# LEDThermometer.net
KiCad netlist of a schematic drawn in Altium Designer
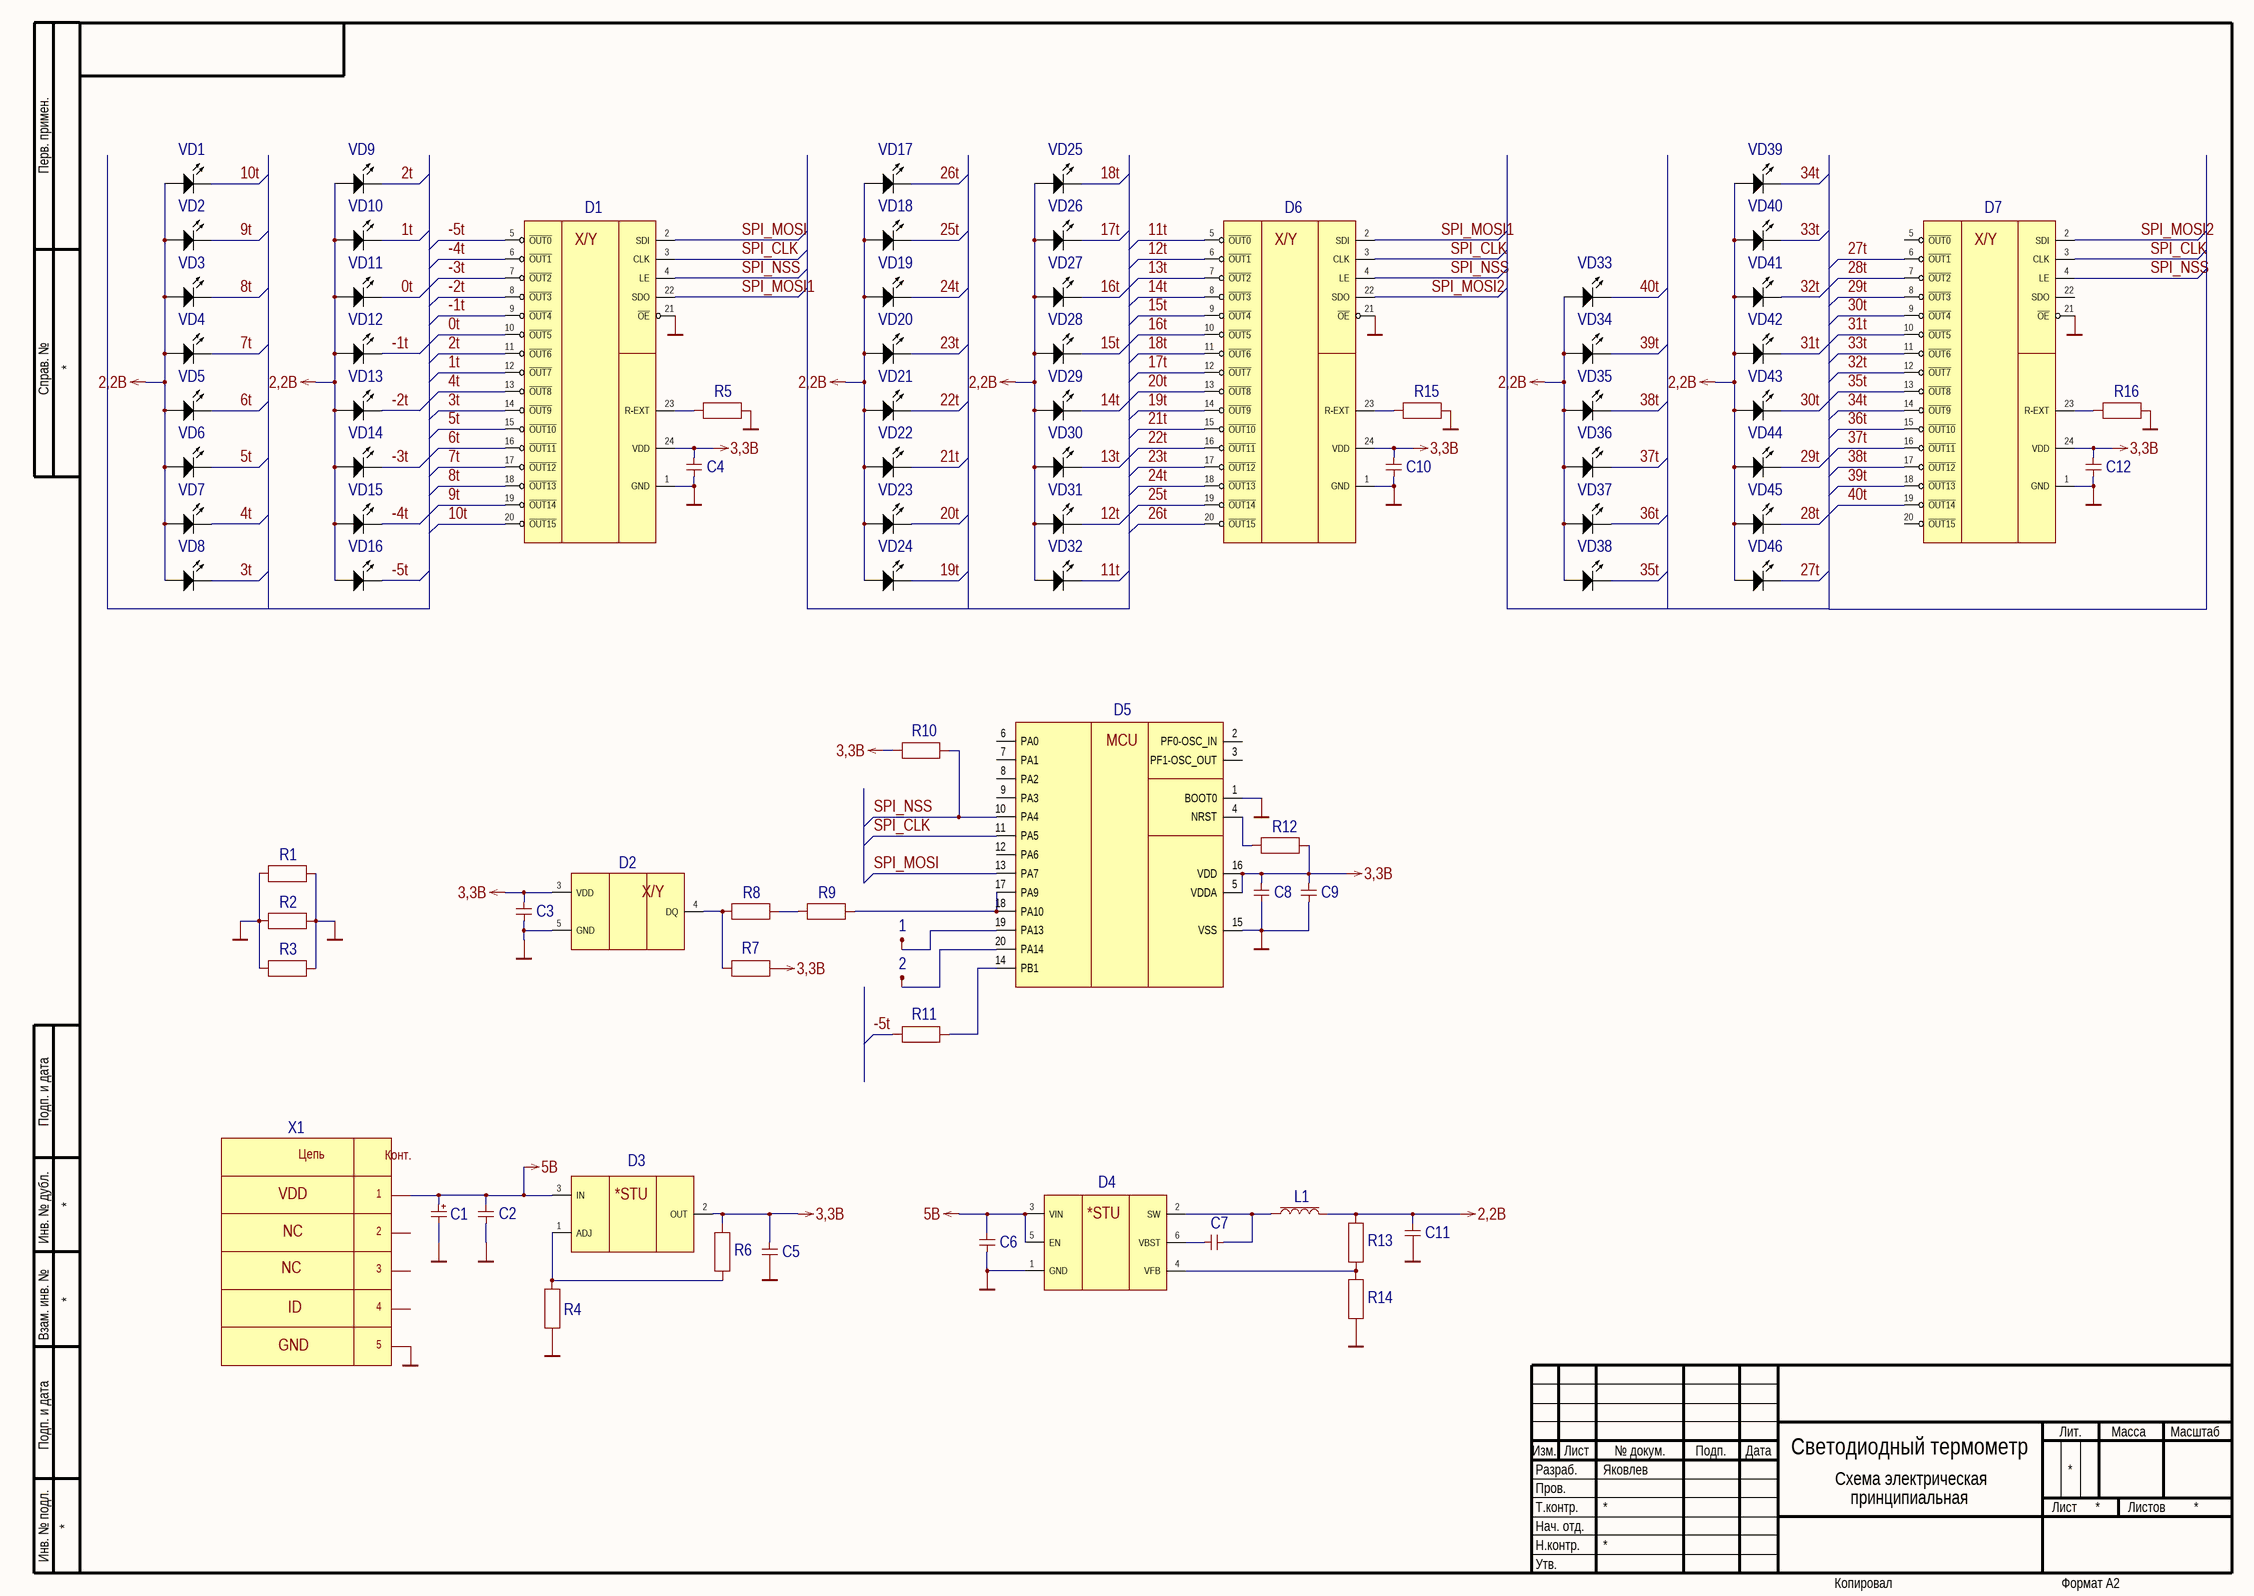
[diagram p0: LEDThermometer.SchDoc]

(export (version "E")
  (design (tool "Eeschema 10.0.6"))
  (components
    (comp (ref "1") (value "*") (footprint "point") (libsource (lib "Passive,Diodes") (part "Point")))
    (comp (ref "2") (value "*") (footprint "point") (libsource (lib "Passive,Diodes") (part "Point")))
    (comp (ref "C1")
      (value "D-20 В-47 мкФ±10 %")
      (footprint "CAP POL 2917/7343")
      (description "Electrolytic capacitor")
      (libsource (lib "Passive,Diodes") (part "Cap_el"))
    )
    (comp (ref "C2")
      (value "0805-16 В-X7R-1мкФ±10 %")
      (footprint "SMD-0805C")
      (description "Capacitor")
      (libsource (lib "Passive,Diodes") (part "Cap"))
    )
    (comp (ref "C3")
      (value "0805-16 В-X7R-0,1мкФ±10 %")
      (footprint "SMD-0805C")
      (description "Capacitor")
      (libsource (lib "Passive,Diodes") (part "Cap"))
    )
    (comp (ref "C4")
      (value "0805-16 В-X7R-0,1мкФ±10 %")
      (footprint "SMD-0805C")
      (description "Capacitor")
      (libsource (lib "Passive,Diodes") (part "Cap"))
    )
    (comp (ref "C5")
      (value "0805-16 В-X7R-1мкФ±10 %")
      (footprint "SMD-0805C")
      (description "Capacitor")
      (libsource (lib "Passive,Diodes") (part "Cap"))
    )
    (comp (ref "C6")
      (value "0805-16 В-X7R-0,1мкФ±10 %")
      (footprint "SMD-0805C")
      (description "Capacitor")
      (libsource (lib "Passive,Diodes") (part "Cap"))
    )
    (comp (ref "C7")
      (value "0805-16 В-X7R-0,1мкФ±10 %")
      (footprint "SMD-0805C")
      (description "Capacitor")
      (libsource (lib "Passive,Diodes") (part "Cap"))
    )
    (comp (ref "C8")
      (value "0805-16 В-X7R-0,1мкФ±10 %")
      (footprint "SMD-0805C")
      (description "Capacitor")
      (libsource (lib "Passive,Diodes") (part "Cap"))
    )
    (comp (ref "C9")
      (value "0805-16 В-X7R-0,1мкФ±10 %")
      (footprint "SMD-0805C")
      (description "Capacitor")
      (libsource (lib "Passive,Diodes") (part "Cap"))
    )
    (comp (ref "C10")
      (value "0805-16 В-X7R-0,1мкФ±10 %")
      (footprint "SMD-0805C")
      (description "Capacitor")
      (libsource (lib "Passive,Diodes") (part "Cap"))
    )
    (comp (ref "C11")
      (value "1206-16 В-X7R-22мкФ±10 %")
      (footprint "SMD-1206C")
      (description "Capacitor")
      (libsource (lib "Passive,Diodes") (part "Cap"))
    )
    (comp (ref "C12")
      (value "0805-16 В-X7R-0,1мкФ±10 %")
      (footprint "SMD-0805C")
      (description "Capacitor")
      (libsource (lib "Passive,Diodes") (part "Cap"))
    )
    (comp (ref "D1")
      (value "MBI5039GF-B")
      (footprint "SOP24L")
      (description "16-Channel Constant Current LED Sink Driver with Silent Error Detection and Current Gain")
      (fields (field (name "MANUFACTURER") "Macroblock"))
      (libsource (lib "Devices") (part "MBI5039"))
    )
    (comp (ref "D2")
      (value "DS18B20Z+")
      (footprint "SO8_M")
      (description "Programmable Resolution 1-Wire Digital Thermometer")
      (fields (field (name "MANUFACTURER") "Maxim Integrated"))
      (libsource (lib "Devices") (part "DS18B20"))
    )
    (comp (ref "D3")
      (value "LM317DCYR")
      (footprint "SOT223_M")
      (description "3-Terminal Adjustable Regulator")
      (fields (field (name "MANUFACTURER") "Texas Instruments"))
      (libsource (lib "Devices") (part "LM317"))
    )
    (comp (ref "D4")
      (value "TPS562200DDCT")
      (footprint "SOT23-6_M")
      (description "4.5-V To 17-V Input, 2-A, 3-A Synchronous Step-Down Voltage Regulator")
      (fields (field (name "MANUFACTURER") "Texas Instruments"))
      (libsource (lib "Devices") (part "TPS562200"))
    )
    (comp (ref "D5")
      (value "STM32F030F4P6")
      (footprint "TSSOP-20")
      (fields (field (name "MANUFACTURER") "STMicroelectronics"))
      (libsource (lib "Devices") (part "STM32F030F"))
    )
    (comp (ref "D6")
      (value "MBI5039GF-B")
      (footprint "SOP24L")
      (description "16-Channel Constant Current LED Sink Driver with Silent Error Detection and Current Gain")
      (fields (field (name "MANUFACTURER") "Macroblock"))
      (libsource (lib "Devices") (part "MBI5039"))
    )
    (comp (ref "D7")
      (value "MBI5039GF-B")
      (footprint "SOP24L")
      (description "16-Channel Constant Current LED Sink Driver with Silent Error Detection and Current Gain")
      (fields (field (name "MANUFACTURER") "Macroblock"))
      (libsource (lib "Devices") (part "MBI5039"))
    )
    (comp (ref "L1")
      (value "NLCV32T-2R2M-EF")
      (footprint "1210_M")
      (description "Inductor")
      (fields (field (name "MANUFACTURER") "TDK"))
      (libsource (lib "Passive,Diodes") (part "Inductor"))
    )
    (comp (ref "R1")
      (value "0805±5 %-0 Ом")
      (footprint "SMD-0805-RES")
      (description "Resistor")
      (libsource (lib "Passive,Diodes") (part "Res"))
    )
    (comp (ref "R2")
      (value "0805±5 %-0 Ом")
      (footprint "SMD-0805-RES")
      (description "Resistor")
      (libsource (lib "Passive,Diodes") (part "Res"))
    )
    (comp (ref "R3")
      (value "0805±5 %-0 Ом")
      (footprint "SMD-0805-RES")
      (description "Resistor")
      (libsource (lib "Passive,Diodes") (part "Res"))
    )
    (comp (ref "R4")
      (value "0805±1 %-2 кОм")
      (footprint "SMD-0805-RES")
      (description "Resistor")
      (libsource (lib "") (part "Res_3"))
    )
    (comp (ref "R5")
      (value "0805±1 %-10 кОм")
      (footprint "SMD-0805-RES")
      (description "Resistor")
      (libsource (lib "Passive,Diodes") (part "Res"))
    )
    (comp (ref "R6")
      (value "0805±1 %-1,3 кОм")
      (footprint "SMD-0805-RES")
      (description "Resistor")
      (libsource (lib "Passive,Diodes") (part "Res"))
    )
    (comp (ref "R7")
      (value "0805±5 %-4,7 кОм")
      (footprint "SMD-0805-RES")
      (description "Resistor")
      (libsource (lib "") (part "Res_2"))
    )
    (comp (ref "R8")
      (value "0805±5 %-0 Ом")
      (footprint "SMD-0805-RES")
      (description "Resistor")
      (libsource (lib "Passive,Diodes") (part "Res"))
    )
    (comp (ref "R9")
      (value "0805±5 %-0 Ом")
      (footprint "SMD-0805-RES")
      (description "Resistor")
      (libsource (lib "Passive,Diodes") (part "Res"))
    )
    (comp (ref "R10")
      (value "0805±5 %-10 кОм")
      (footprint "SMD-0805-RES")
      (description "Resistor")
      (libsource (lib "") (part "Res_1"))
    )
    (comp (ref "R11")
      (value "не устанавливать")
      (footprint "SMD-0805-RES")
      (description "Resistor")
      (libsource (lib "") (part "Res_1"))
    )
    (comp (ref "R12")
      (value "0805±5 %-10 кОм")
      (footprint "SMD-0805-RES")
      (description "Resistor")
      (libsource (lib "Passive,Diodes") (part "Res"))
    )
    (comp (ref "R13")
      (value "0805±1 %-19,6 кОм")
      (footprint "SMD-0805-RES")
      (description "Resistor")
      (libsource (lib "Passive,Diodes") (part "Res"))
    )
    (comp (ref "R14")
      (value "0805±1 %-10,2 кОм")
      (footprint "SMD-0805-RES")
      (description "Resistor")
      (libsource (lib "Passive,Diodes") (part "Res"))
    )
    (comp (ref "R15")
      (value "0805±1 %-10 кОм")
      (footprint "SMD-0805-RES")
      (description "Resistor")
      (libsource (lib "Passive,Diodes") (part "Res"))
    )
    (comp (ref "R16")
      (value "0805±1 %-10 кОм")
      (footprint "SMD-0805-RES")
      (description "Resistor")
      (libsource (lib "Passive,Diodes") (part "Res"))
    )
    (comp (ref "VD1")
      (value "L-144IDT")
      (footprint "LED_1.9x3.9mm")
      (description "Typical INFRARED GaAs LED")
      (fields (field (name "MANUFACTURER") "Kingbright"))
      (libsource (lib "Passive,Diodes") (part "LED"))
    )
    (comp (ref "VD2")
      (value "L-144IDT")
      (footprint "LED_1.9x3.9mm")
      (description "Typical INFRARED GaAs LED")
      (fields (field (name "MANUFACTURER") "Kingbright"))
      (libsource (lib "Passive,Diodes") (part "LED"))
    )
    (comp (ref "VD3")
      (value "L-144IDT")
      (footprint "LED_1.9x3.9mm")
      (description "Typical INFRARED GaAs LED")
      (fields (field (name "MANUFACTURER") "Kingbright"))
      (libsource (lib "Passive,Diodes") (part "LED"))
    )
    (comp (ref "VD4")
      (value "L-144IDT")
      (footprint "LED_1.9x3.9mm")
      (description "Typical INFRARED GaAs LED")
      (fields (field (name "MANUFACTURER") "Kingbright"))
      (libsource (lib "Passive,Diodes") (part "LED"))
    )
    (comp (ref "VD5")
      (value "L-144IDT")
      (footprint "LED_1.9x3.9mm")
      (description "Typical INFRARED GaAs LED")
      (fields (field (name "MANUFACTURER") "Kingbright"))
      (libsource (lib "Passive,Diodes") (part "LED"))
    )
    (comp (ref "VD6")
      (value "L-144IDT")
      (footprint "LED_1.9x3.9mm")
      (description "Typical INFRARED GaAs LED")
      (fields (field (name "MANUFACTURER") "Kingbright"))
      (libsource (lib "Passive,Diodes") (part "LED"))
    )
    (comp (ref "VD7")
      (value "L-144IDT")
      (footprint "LED_1.9x3.9mm")
      (description "Typical INFRARED GaAs LED")
      (fields (field (name "MANUFACTURER") "Kingbright"))
      (libsource (lib "Passive,Diodes") (part "LED"))
    )
    (comp (ref "VD8")
      (value "L-144IDT")
      (footprint "LED_1.9x3.9mm")
      (description "Typical INFRARED GaAs LED")
      (fields (field (name "MANUFACTURER") "Kingbright"))
      (libsource (lib "Passive,Diodes") (part "LED"))
    )
    (comp (ref "VD9")
      (value "L-144IDT")
      (footprint "LED_1.9x3.9mm")
      (description "Typical INFRARED GaAs LED")
      (fields (field (name "MANUFACTURER") "Kingbright"))
      (libsource (lib "Passive,Diodes") (part "LED"))
    )
    (comp (ref "VD10")
      (value "L-144IDT")
      (footprint "LED_1.9x3.9mm")
      (description "Typical INFRARED GaAs LED")
      (fields (field (name "MANUFACTURER") "Kingbright"))
      (libsource (lib "Passive,Diodes") (part "LED"))
    )
    (comp (ref "VD11")
      (value "L-144IDT")
      (footprint "LED_1.9x3.9mm")
      (description "Typical INFRARED GaAs LED")
      (fields (field (name "MANUFACTURER") "Kingbright"))
      (libsource (lib "Passive,Diodes") (part "LED"))
    )
    (comp (ref "VD12")
      (value "L-144IDT")
      (footprint "LED_1.9x3.9mm")
      (description "Typical INFRARED GaAs LED")
      (fields (field (name "MANUFACTURER") "Kingbright"))
      (libsource (lib "Passive,Diodes") (part "LED"))
    )
    (comp (ref "VD13")
      (value "L-144IDT")
      (footprint "LED_1.9x3.9mm")
      (description "Typical INFRARED GaAs LED")
      (fields (field (name "MANUFACTURER") "Kingbright"))
      (libsource (lib "Passive,Diodes") (part "LED"))
    )
    (comp (ref "VD14")
      (value "L-144IDT")
      (footprint "LED_1.9x3.9mm")
      (description "Typical INFRARED GaAs LED")
      (fields (field (name "MANUFACTURER") "Kingbright"))
      (libsource (lib "Passive,Diodes") (part "LED"))
    )
    (comp (ref "VD15")
      (value "L-144IDT")
      (footprint "LED_1.9x3.9mm")
      (description "Typical INFRARED GaAs LED")
      (fields (field (name "MANUFACTURER") "Kingbright"))
      (libsource (lib "Passive,Diodes") (part "LED"))
    )
    (comp (ref "VD16")
      (value "L-793ID")
      (footprint "LED_8mm")
      (description "Typical INFRARED GaAs LED")
      (fields (field (name "MANUFACTURER") "Kingbright"))
      (libsource (lib "Passive,Diodes") (part "LED"))
    )
    (comp (ref "VD17")
      (value "L-144IDT")
      (footprint "LED_1.9x3.9mm")
      (description "Typical INFRARED GaAs LED")
      (fields (field (name "MANUFACTURER") "Kingbright"))
      (libsource (lib "Passive,Diodes") (part "LED"))
    )
    (comp (ref "VD18")
      (value "L-144IDT")
      (footprint "LED_1.9x3.9mm")
      (description "Typical INFRARED GaAs LED")
      (fields (field (name "MANUFACTURER") "Kingbright"))
      (libsource (lib "Passive,Diodes") (part "LED"))
    )
    (comp (ref "VD19")
      (value "L-144IDT")
      (footprint "LED_1.9x3.9mm")
      (description "Typical INFRARED GaAs LED")
      (fields (field (name "MANUFACTURER") "Kingbright"))
      (libsource (lib "Passive,Diodes") (part "LED"))
    )
    (comp (ref "VD20")
      (value "L-144IDT")
      (footprint "LED_1.9x3.9mm")
      (description "Typical INFRARED GaAs LED")
      (fields (field (name "MANUFACTURER") "Kingbright"))
      (libsource (lib "Passive,Diodes") (part "LED"))
    )
    (comp (ref "VD21")
      (value "L-144IDT")
      (footprint "LED_1.9x3.9mm")
      (description "Typical INFRARED GaAs LED")
      (fields (field (name "MANUFACTURER") "Kingbright"))
      (libsource (lib "Passive,Diodes") (part "LED"))
    )
    (comp (ref "VD22")
      (value "L-144IDT")
      (footprint "LED_1.9x3.9mm")
      (description "Typical INFRARED GaAs LED")
      (fields (field (name "MANUFACTURER") "Kingbright"))
      (libsource (lib "Passive,Diodes") (part "LED"))
    )
    (comp (ref "VD23")
      (value "L-144IDT")
      (footprint "LED_1.9x3.9mm")
      (description "Typical INFRARED GaAs LED")
      (fields (field (name "MANUFACTURER") "Kingbright"))
      (libsource (lib "Passive,Diodes") (part "LED"))
    )
    (comp (ref "VD24")
      (value "L-144IDT")
      (footprint "LED_1.9x3.9mm")
      (description "Typical INFRARED GaAs LED")
      (fields (field (name "MANUFACTURER") "Kingbright"))
      (libsource (lib "Passive,Diodes") (part "LED"))
    )
    (comp (ref "VD25")
      (value "L-144IDT")
      (footprint "LED_1.9x3.9mm")
      (description "Typical INFRARED GaAs LED")
      (fields (field (name "MANUFACTURER") "Kingbright"))
      (libsource (lib "Passive,Diodes") (part "LED"))
    )
    (comp (ref "VD26")
      (value "L-144IDT")
      (footprint "LED_1.9x3.9mm")
      (description "Typical INFRARED GaAs LED")
      (fields (field (name "MANUFACTURER") "Kingbright"))
      (libsource (lib "Passive,Diodes") (part "LED"))
    )
    (comp (ref "VD27")
      (value "L-144IDT")
      (footprint "LED_1.9x3.9mm")
      (description "Typical INFRARED GaAs LED")
      (fields (field (name "MANUFACTURER") "Kingbright"))
      (libsource (lib "Passive,Diodes") (part "LED"))
    )
    (comp (ref "VD28")
      (value "L-144IDT")
      (footprint "LED_1.9x3.9mm")
      (description "Typical INFRARED GaAs LED")
      (fields (field (name "MANUFACTURER") "Kingbright"))
      (libsource (lib "Passive,Diodes") (part "LED"))
    )
    (comp (ref "VD29")
      (value "L-144IDT")
      (footprint "LED_1.9x3.9mm")
      (description "Typical INFRARED GaAs LED")
      (fields (field (name "MANUFACTURER") "Kingbright"))
      (libsource (lib "Passive,Diodes") (part "LED"))
    )
    (comp (ref "VD30")
      (value "L-144IDT")
      (footprint "LED_1.9x3.9mm")
      (description "Typical INFRARED GaAs LED")
      (fields (field (name "MANUFACTURER") "Kingbright"))
      (libsource (lib "Passive,Diodes") (part "LED"))
    )
    (comp (ref "VD31")
      (value "L-144IDT")
      (footprint "LED_1.9x3.9mm")
      (description "Typical INFRARED GaAs LED")
      (fields (field (name "MANUFACTURER") "Kingbright"))
      (libsource (lib "Passive,Diodes") (part "LED"))
    )
    (comp (ref "VD32")
      (value "L-144IDT")
      (footprint "LED_1.9x3.9mm")
      (description "Typical INFRARED GaAs LED")
      (fields (field (name "MANUFACTURER") "Kingbright"))
      (libsource (lib "Passive,Diodes") (part "LED"))
    )
    (comp (ref "VD33")
      (value "L-144IDT")
      (footprint "LED_1.9x3.9mm")
      (description "Typical INFRARED GaAs LED")
      (fields (field (name "MANUFACTURER") "Kingbright"))
      (libsource (lib "Passive,Diodes") (part "LED"))
    )
    (comp (ref "VD34")
      (value "L-144IDT")
      (footprint "LED_1.9x3.9mm")
      (description "Typical INFRARED GaAs LED")
      (fields (field (name "MANUFACTURER") "Kingbright"))
      (libsource (lib "Passive,Diodes") (part "LED"))
    )
    (comp (ref "VD35")
      (value "L-144IDT")
      (footprint "LED_1.9x3.9mm")
      (description "Typical INFRARED GaAs LED")
      (fields (field (name "MANUFACTURER") "Kingbright"))
      (libsource (lib "Passive,Diodes") (part "LED"))
    )
    (comp (ref "VD36")
      (value "L-144IDT")
      (footprint "LED_1.9x3.9mm")
      (description "Typical INFRARED GaAs LED")
      (fields (field (name "MANUFACTURER") "Kingbright"))
      (libsource (lib "Passive,Diodes") (part "LED"))
    )
    (comp (ref "VD37")
      (value "L-144IDT")
      (footprint "LED_1.9x3.9mm")
      (description "Typical INFRARED GaAs LED")
      (fields (field (name "MANUFACTURER") "Kingbright"))
      (libsource (lib "Passive,Diodes") (part "LED"))
    )
    (comp (ref "VD38")
      (value "L-144IDT")
      (footprint "LED_1.9x3.9mm")
      (description "Typical INFRARED GaAs LED")
      (fields (field (name "MANUFACTURER") "Kingbright"))
      (libsource (lib "Passive,Diodes") (part "LED"))
    )
    (comp (ref "VD39")
      (value "L-144IDT")
      (footprint "LED_1.9x3.9mm")
      (description "Typical INFRARED GaAs LED")
      (fields (field (name "MANUFACTURER") "Kingbright"))
      (libsource (lib "Passive,Diodes") (part "LED"))
    )
    (comp (ref "VD40")
      (value "L-144IDT")
      (footprint "LED_1.9x3.9mm")
      (description "Typical INFRARED GaAs LED")
      (fields (field (name "MANUFACTURER") "Kingbright"))
      (libsource (lib "Passive,Diodes") (part "LED"))
    )
    (comp (ref "VD41")
      (value "L-144IDT")
      (footprint "LED_1.9x3.9mm")
      (description "Typical INFRARED GaAs LED")
      (fields (field (name "MANUFACTURER") "Kingbright"))
      (libsource (lib "Passive,Diodes") (part "LED"))
    )
    (comp (ref "VD42")
      (value "L-144IDT")
      (footprint "LED_1.9x3.9mm")
      (description "Typical INFRARED GaAs LED")
      (fields (field (name "MANUFACTURER") "Kingbright"))
      (libsource (lib "Passive,Diodes") (part "LED"))
    )
    (comp (ref "VD43")
      (value "L-144IDT")
      (footprint "LED_1.9x3.9mm")
      (description "Typical INFRARED GaAs LED")
      (fields (field (name "MANUFACTURER") "Kingbright"))
      (libsource (lib "Passive,Diodes") (part "LED"))
    )
    (comp (ref "VD44")
      (value "L-144IDT")
      (footprint "LED_1.9x3.9mm")
      (description "Typical INFRARED GaAs LED")
      (fields (field (name "MANUFACTURER") "Kingbright"))
      (libsource (lib "Passive,Diodes") (part "LED"))
    )
    (comp (ref "VD45")
      (value "L-144IDT")
      (footprint "LED_1.9x3.9mm")
      (description "Typical INFRARED GaAs LED")
      (fields (field (name "MANUFACTURER") "Kingbright"))
      (libsource (lib "Passive,Diodes") (part "LED"))
    )
    (comp (ref "VD46")
      (value "L-144IDT")
      (footprint "LED_1.9x3.9mm")
      (description "Typical INFRARED GaAs LED")
      (fields (field (name "MANUFACTURER") "Kingbright"))
      (libsource (lib "Passive,Diodes") (part "LED"))
    )
    (comp (ref "X1")
      (value "DS1104-B60SRS")
      (footprint "Mini-USB-B")
      (description "Mini USB-B connector")
      (fields (field (name "MANUFACTURER") "Connfly Electronics"))
      (libsource (lib "Connectors") (part "MINI-USB-B"))
    )
  )
  (nets
    (net (code "1") (name "/-1t") (class "Default")
      (node (ref "D1") (pin "9") (pinfunction "~{OUT4}_9") (pintype "passive"))
      (node (ref "VD12") (pin "2") (pinfunction "K_2") (pintype "passive"))
    )
    (net (code "2") (name "/-2t") (class "Default")
      (node (ref "D1") (pin "8") (pinfunction "~{OUT3}_8") (pintype "passive"))
      (node (ref "VD13") (pin "2") (pinfunction "K_2") (pintype "passive"))
    )
    (net (code "3") (name "/-3t") (class "Default")
      (node (ref "D1") (pin "7") (pinfunction "~{OUT2}_7") (pintype "passive"))
      (node (ref "VD14") (pin "2") (pinfunction "K_2") (pintype "passive"))
    )
    (net (code "4") (name "/-4t") (class "Default")
      (node (ref "D1") (pin "6") (pinfunction "~{OUT1}_6") (pintype "passive"))
      (node (ref "VD15") (pin "2") (pinfunction "K_2") (pintype "passive"))
    )
    (net (code "5") (name "/-5t") (class "Default")
      (node (ref "D1") (pin "5") (pinfunction "~{OUT0}_5") (pintype "passive"))
      (node (ref "R11") (pin "1") (pinfunction "1_1") (pintype "passive"))
      (node (ref "VD16") (pin "2") (pinfunction "K_2") (pintype "passive"))
    )
    (net (code "6") (name "/0t") (class "Default")
      (node (ref "D1") (pin "10") (pinfunction "~{OUT5}_10") (pintype "passive"))
      (node (ref "VD11") (pin "2") (pinfunction "K_2") (pintype "passive"))
    )
    (net (code "7") (name "/1t") (class "Default")
      (node (ref "D1") (pin "12") (pinfunction "~{OUT7}_12") (pintype "passive"))
      (node (ref "VD10") (pin "2") (pinfunction "K_2") (pintype "passive"))
    )
    (net (code "8") (name "/2t") (class "Default")
      (node (ref "D1") (pin "11") (pinfunction "~{OUT6}_11") (pintype "passive"))
      (node (ref "VD9") (pin "2") (pinfunction "K_2") (pintype "passive"))
    )
    (net (code "9") (name "/3t") (class "Default")
      (node (ref "D1") (pin "14") (pinfunction "~{OUT9}_14") (pintype "passive"))
      (node (ref "VD8") (pin "2") (pinfunction "K_2") (pintype "passive"))
    )
    (net (code "10") (name "/4t") (class "Default")
      (node (ref "D1") (pin "13") (pinfunction "~{OUT8}_13") (pintype "passive"))
      (node (ref "VD7") (pin "2") (pinfunction "K_2") (pintype "passive"))
    )
    (net (code "11") (name "/5t") (class "Default")
      (node (ref "D1") (pin "15") (pinfunction "~{OUT10}_15") (pintype "passive"))
      (node (ref "VD6") (pin "2") (pinfunction "K_2") (pintype "passive"))
    )
    (net (code "12") (name "/6t") (class "Default")
      (node (ref "D1") (pin "16") (pinfunction "~{OUT11}_16") (pintype "passive"))
      (node (ref "VD5") (pin "2") (pinfunction "K_2") (pintype "passive"))
    )
    (net (code "13") (name "/7t") (class "Default")
      (node (ref "D1") (pin "17") (pinfunction "~{OUT12}_17") (pintype "passive"))
      (node (ref "VD4") (pin "2") (pinfunction "K_2") (pintype "passive"))
    )
    (net (code "14") (name "/8t") (class "Default")
      (node (ref "D1") (pin "18") (pinfunction "~{OUT13}_18") (pintype "passive"))
      (node (ref "VD3") (pin "2") (pinfunction "K_2") (pintype "passive"))
    )
    (net (code "15") (name "/9t") (class "Default")
      (node (ref "D1") (pin "19") (pinfunction "~{OUT14}_19") (pintype "passive"))
      (node (ref "VD2") (pin "2") (pinfunction "K_2") (pintype "passive"))
    )
    (net (code "16") (name "/10t") (class "Default")
      (node (ref "D1") (pin "20") (pinfunction "~{OUT15}_20") (pintype "passive"))
      (node (ref "VD1") (pin "2") (pinfunction "K_2") (pintype "passive"))
    )
    (net (code "17") (name "/11t") (class "Default")
      (node (ref "D6") (pin "5") (pinfunction "~{OUT0}_5") (pintype "passive"))
      (node (ref "VD32") (pin "2") (pinfunction "K_2") (pintype "passive"))
    )
    (net (code "18") (name "/12t") (class "Default")
      (node (ref "D6") (pin "6") (pinfunction "~{OUT1}_6") (pintype "passive"))
      (node (ref "VD31") (pin "2") (pinfunction "K_2") (pintype "passive"))
    )
    (net (code "19") (name "/13t") (class "Default")
      (node (ref "D6") (pin "7") (pinfunction "~{OUT2}_7") (pintype "passive"))
      (node (ref "VD30") (pin "2") (pinfunction "K_2") (pintype "passive"))
    )
    (net (code "20") (name "/14t") (class "Default")
      (node (ref "D6") (pin "8") (pinfunction "~{OUT3}_8") (pintype "passive"))
      (node (ref "VD29") (pin "2") (pinfunction "K_2") (pintype "passive"))
    )
    (net (code "21") (name "/15t") (class "Default")
      (node (ref "D6") (pin "9") (pinfunction "~{OUT4}_9") (pintype "passive"))
      (node (ref "VD28") (pin "2") (pinfunction "K_2") (pintype "passive"))
    )
    (net (code "22") (name "/16t") (class "Default")
      (node (ref "D6") (pin "10") (pinfunction "~{OUT5}_10") (pintype "passive"))
      (node (ref "VD27") (pin "2") (pinfunction "K_2") (pintype "passive"))
    )
    (net (code "23") (name "/17t") (class "Default")
      (node (ref "D6") (pin "12") (pinfunction "~{OUT7}_12") (pintype "passive"))
      (node (ref "VD26") (pin "2") (pinfunction "K_2") (pintype "passive"))
    )
    (net (code "24") (name "/18t") (class "Default")
      (node (ref "D6") (pin "11") (pinfunction "~{OUT6}_11") (pintype "passive"))
      (node (ref "VD25") (pin "2") (pinfunction "K_2") (pintype "passive"))
    )
    (net (code "25") (name "/19t") (class "Default")
      (node (ref "D6") (pin "14") (pinfunction "~{OUT9}_14") (pintype "passive"))
      (node (ref "VD24") (pin "2") (pinfunction "K_2") (pintype "passive"))
    )
    (net (code "26") (name "/20t") (class "Default")
      (node (ref "D6") (pin "13") (pinfunction "~{OUT8}_13") (pintype "passive"))
      (node (ref "VD23") (pin "2") (pinfunction "K_2") (pintype "passive"))
    )
    (net (code "27") (name "/21t") (class "Default")
      (node (ref "D6") (pin "15") (pinfunction "~{OUT10}_15") (pintype "passive"))
      (node (ref "VD22") (pin "2") (pinfunction "K_2") (pintype "passive"))
    )
    (net (code "28") (name "/22t") (class "Default")
      (node (ref "D6") (pin "16") (pinfunction "~{OUT11}_16") (pintype "passive"))
      (node (ref "VD21") (pin "2") (pinfunction "K_2") (pintype "passive"))
    )
    (net (code "29") (name "/23t") (class "Default")
      (node (ref "D6") (pin "17") (pinfunction "~{OUT12}_17") (pintype "passive"))
      (node (ref "VD20") (pin "2") (pinfunction "K_2") (pintype "passive"))
    )
    (net (code "30") (name "/24t") (class "Default")
      (node (ref "D6") (pin "18") (pinfunction "~{OUT13}_18") (pintype "passive"))
      (node (ref "VD19") (pin "2") (pinfunction "K_2") (pintype "passive"))
    )
    (net (code "31") (name "/25t") (class "Default")
      (node (ref "D6") (pin "19") (pinfunction "~{OUT14}_19") (pintype "passive"))
      (node (ref "VD18") (pin "2") (pinfunction "K_2") (pintype "passive"))
    )
    (net (code "32") (name "/26t") (class "Default")
      (node (ref "D6") (pin "20") (pinfunction "~{OUT15}_20") (pintype "passive"))
      (node (ref "VD17") (pin "2") (pinfunction "K_2") (pintype "passive"))
    )
    (net (code "33") (name "/27t") (class "Default")
      (node (ref "D7") (pin "6") (pinfunction "~{OUT1}_6") (pintype "passive"))
      (node (ref "VD46") (pin "2") (pinfunction "K_2") (pintype "passive"))
    )
    (net (code "34") (name "/28t") (class "Default")
      (node (ref "D7") (pin "7") (pinfunction "~{OUT2}_7") (pintype "passive"))
      (node (ref "VD45") (pin "2") (pinfunction "K_2") (pintype "passive"))
    )
    (net (code "35") (name "/29t") (class "Default")
      (node (ref "D7") (pin "8") (pinfunction "~{OUT3}_8") (pintype "passive"))
      (node (ref "VD44") (pin "2") (pinfunction "K_2") (pintype "passive"))
    )
    (net (code "36") (name "/30t") (class "Default")
      (node (ref "D7") (pin "9") (pinfunction "~{OUT4}_9") (pintype "passive"))
      (node (ref "VD43") (pin "2") (pinfunction "K_2") (pintype "passive"))
    )
    (net (code "37") (name "/31t") (class "Default")
      (node (ref "D7") (pin "10") (pinfunction "~{OUT5}_10") (pintype "passive"))
      (node (ref "VD42") (pin "2") (pinfunction "K_2") (pintype "passive"))
    )
    (net (code "38") (name "/32t") (class "Default")
      (node (ref "D7") (pin "12") (pinfunction "~{OUT7}_12") (pintype "passive"))
      (node (ref "VD41") (pin "2") (pinfunction "K_2") (pintype "passive"))
    )
    (net (code "39") (name "/33t") (class "Default")
      (node (ref "D7") (pin "11") (pinfunction "~{OUT6}_11") (pintype "passive"))
      (node (ref "VD40") (pin "2") (pinfunction "K_2") (pintype "passive"))
    )
    (net (code "40") (name "/34t") (class "Default")
      (node (ref "D7") (pin "14") (pinfunction "~{OUT9}_14") (pintype "passive"))
      (node (ref "VD39") (pin "2") (pinfunction "K_2") (pintype "passive"))
    )
    (net (code "41") (name "/35t") (class "Default")
      (node (ref "D7") (pin "13") (pinfunction "~{OUT8}_13") (pintype "passive"))
      (node (ref "VD38") (pin "2") (pinfunction "K_2") (pintype "passive"))
    )
    (net (code "42") (name "/36t") (class "Default")
      (node (ref "D7") (pin "15") (pinfunction "~{OUT10}_15") (pintype "passive"))
      (node (ref "VD37") (pin "2") (pinfunction "K_2") (pintype "passive"))
    )
    (net (code "43") (name "/37t") (class "Default")
      (node (ref "D7") (pin "16") (pinfunction "~{OUT11}_16") (pintype "passive"))
      (node (ref "VD36") (pin "2") (pinfunction "K_2") (pintype "passive"))
    )
    (net (code "44") (name "/38t") (class "Default")
      (node (ref "D7") (pin "17") (pinfunction "~{OUT12}_17") (pintype "passive"))
      (node (ref "VD35") (pin "2") (pinfunction "K_2") (pintype "passive"))
    )
    (net (code "45") (name "/39t") (class "Default")
      (node (ref "D7") (pin "18") (pinfunction "~{OUT13}_18") (pintype "passive"))
      (node (ref "VD34") (pin "2") (pinfunction "K_2") (pintype "passive"))
    )
    (net (code "46") (name "/40t") (class "Default")
      (node (ref "D7") (pin "19") (pinfunction "~{OUT14}_19") (pintype "passive"))
      (node (ref "VD33") (pin "2") (pinfunction "K_2") (pintype "passive"))
    )
    (net (code "47") (name "/SPI_CLK") (class "Default")
      (node (ref "D1") (pin "3") (pinfunction "CLK_3") (pintype "passive"))
      (node (ref "D5") (pin "11") (pinfunction "PA5_11") (pintype "passive"))
      (node (ref "D6") (pin "3") (pinfunction "CLK_3") (pintype "passive"))
      (node (ref "D7") (pin "3") (pinfunction "CLK_3") (pintype "passive"))
    )
    (net (code "48") (name "/SPI_MOSI") (class "Default")
      (node (ref "D1") (pin "2") (pinfunction "SDI_2") (pintype "passive"))
      (node (ref "D5") (pin "13") (pinfunction "PA7_13") (pintype "passive"))
    )
    (net (code "49") (name "/SPI_MOSI1") (class "Default")
      (node (ref "D1") (pin "22") (pinfunction "SDO_22") (pintype "passive"))
      (node (ref "D6") (pin "2") (pinfunction "SDI_2") (pintype "passive"))
    )
    (net (code "50") (name "/SPI_MOSI2") (class "Default")
      (node (ref "D6") (pin "22") (pinfunction "SDO_22") (pintype "passive"))
      (node (ref "D7") (pin "2") (pinfunction "SDI_2") (pintype "passive"))
    )
    (net (code "51") (name "/SPI_NSS") (class "Default")
      (node (ref "D1") (pin "4") (pinfunction "LE_4") (pintype "passive"))
      (node (ref "D5") (pin "10") (pinfunction "PA4_10") (pintype "passive"))
      (node (ref "D6") (pin "4") (pinfunction "LE_4") (pintype "passive"))
      (node (ref "D7") (pin "4") (pinfunction "LE_4") (pintype "passive"))
      (node (ref "R10") (pin "2") (pinfunction "2_2") (pintype "passive"))
    )
    (net (code "52") (name "2,2В") (class "Default")
      (node (ref "C11") (pin "2") (pinfunction "2_2") (pintype "passive"))
      (node (ref "L1") (pin "2") (pinfunction "2_2") (pintype "passive"))
      (node (ref "R13") (pin "2") (pinfunction "2_2") (pintype "passive"))
      (node (ref "VD1") (pin "1") (pinfunction "A_1") (pintype "passive"))
      (node (ref "VD10") (pin "1") (pinfunction "A_1") (pintype "passive"))
      (node (ref "VD11") (pin "1") (pinfunction "A_1") (pintype "passive"))
      (node (ref "VD12") (pin "1") (pinfunction "A_1") (pintype "passive"))
      (node (ref "VD13") (pin "1") (pinfunction "A_1") (pintype "passive"))
      (node (ref "VD14") (pin "1") (pinfunction "A_1") (pintype "passive"))
      (node (ref "VD15") (pin "1") (pinfunction "A_1") (pintype "passive"))
      (node (ref "VD16") (pin "1") (pinfunction "A_1") (pintype "passive"))
      (node (ref "VD17") (pin "1") (pinfunction "A_1") (pintype "passive"))
      (node (ref "VD18") (pin "1") (pinfunction "A_1") (pintype "passive"))
      (node (ref "VD19") (pin "1") (pinfunction "A_1") (pintype "passive"))
      (node (ref "VD2") (pin "1") (pinfunction "A_1") (pintype "passive"))
      (node (ref "VD20") (pin "1") (pinfunction "A_1") (pintype "passive"))
      (node (ref "VD21") (pin "1") (pinfunction "A_1") (pintype "passive"))
      (node (ref "VD22") (pin "1") (pinfunction "A_1") (pintype "passive"))
      (node (ref "VD23") (pin "1") (pinfunction "A_1") (pintype "passive"))
      (node (ref "VD24") (pin "1") (pinfunction "A_1") (pintype "passive"))
      (node (ref "VD25") (pin "1") (pinfunction "A_1") (pintype "passive"))
      (node (ref "VD26") (pin "1") (pinfunction "A_1") (pintype "passive"))
      (node (ref "VD27") (pin "1") (pinfunction "A_1") (pintype "passive"))
      (node (ref "VD28") (pin "1") (pinfunction "A_1") (pintype "passive"))
      (node (ref "VD29") (pin "1") (pinfunction "A_1") (pintype "passive"))
      (node (ref "VD3") (pin "1") (pinfunction "A_1") (pintype "passive"))
      (node (ref "VD30") (pin "1") (pinfunction "A_1") (pintype "passive"))
      (node (ref "VD31") (pin "1") (pinfunction "A_1") (pintype "passive"))
      (node (ref "VD32") (pin "1") (pinfunction "A_1") (pintype "passive"))
      (node (ref "VD33") (pin "1") (pinfunction "A_1") (pintype "passive"))
      (node (ref "VD34") (pin "1") (pinfunction "A_1") (pintype "passive"))
      (node (ref "VD35") (pin "1") (pinfunction "A_1") (pintype "passive"))
      (node (ref "VD36") (pin "1") (pinfunction "A_1") (pintype "passive"))
      (node (ref "VD37") (pin "1") (pinfunction "A_1") (pintype "passive"))
      (node (ref "VD38") (pin "1") (pinfunction "A_1") (pintype "passive"))
      (node (ref "VD39") (pin "1") (pinfunction "A_1") (pintype "passive"))
      (node (ref "VD4") (pin "1") (pinfunction "A_1") (pintype "passive"))
      (node (ref "VD40") (pin "1") (pinfunction "A_1") (pintype "passive"))
      (node (ref "VD41") (pin "1") (pinfunction "A_1") (pintype "passive"))
      (node (ref "VD42") (pin "1") (pinfunction "A_1") (pintype "passive"))
      (node (ref "VD43") (pin "1") (pinfunction "A_1") (pintype "passive"))
      (node (ref "VD44") (pin "1") (pinfunction "A_1") (pintype "passive"))
      (node (ref "VD45") (pin "1") (pinfunction "A_1") (pintype "passive"))
      (node (ref "VD46") (pin "1") (pinfunction "A_1") (pintype "passive"))
      (node (ref "VD5") (pin "1") (pinfunction "A_1") (pintype "passive"))
      (node (ref "VD6") (pin "1") (pinfunction "A_1") (pintype "passive"))
      (node (ref "VD7") (pin "1") (pinfunction "A_1") (pintype "passive"))
      (node (ref "VD8") (pin "1") (pinfunction "A_1") (pintype "passive"))
      (node (ref "VD9") (pin "1") (pinfunction "A_1") (pintype "passive"))
    )
    (net (code "53") (name "3,3В") (class "Default")
      (node (ref "C10") (pin "2") (pinfunction "2_2") (pintype "passive"))
      (node (ref "C12") (pin "2") (pinfunction "2_2") (pintype "passive"))
      (node (ref "C3") (pin "2") (pinfunction "2_2") (pintype "passive"))
      (node (ref "C4") (pin "2") (pinfunction "2_2") (pintype "passive"))
      (node (ref "C5") (pin "2") (pinfunction "2_2") (pintype "passive"))
      (node (ref "C8") (pin "2") (pinfunction "2_2") (pintype "passive"))
      (node (ref "C9") (pin "2") (pinfunction "2_2") (pintype "passive"))
      (node (ref "D1") (pin "24") (pinfunction "VDD_24") (pintype "power_in"))
      (node (ref "D2") (pin "3") (pinfunction "VDD_3") (pintype "passive"))
      (node (ref "D3") (pin "2") (pinfunction "OUT_2") (pintype "power_in"))
      (node (ref "D5") (pin "16") (pinfunction "VDD_16") (pintype "power_in"))
      (node (ref "D5") (pin "5") (pinfunction "VDDA_5") (pintype "power_in"))
      (node (ref "D6") (pin "24") (pinfunction "VDD_24") (pintype "power_in"))
      (node (ref "D7") (pin "24") (pinfunction "VDD_24") (pintype "power_in"))
      (node (ref "R10") (pin "1") (pinfunction "1_1") (pintype "passive"))
      (node (ref "R12") (pin "2") (pinfunction "2_2") (pintype "passive"))
      (node (ref "R6") (pin "2") (pinfunction "2_2") (pintype "passive"))
      (node (ref "R7") (pin "1") (pinfunction "1_1") (pintype "passive"))
    )
    (net (code "54") (name "5В") (class "Default")
      (node (ref "C1") (pin "1") (pinfunction "1_1") (pintype "passive"))
      (node (ref "C2") (pin "2") (pinfunction "2_2") (pintype "passive"))
      (node (ref "C6") (pin "2") (pinfunction "2_2") (pintype "passive"))
      (node (ref "D3") (pin "3") (pinfunction "IN_3") (pintype "power_in"))
      (node (ref "D4") (pin "3") (pinfunction "VIN_3") (pintype "power_in"))
      (node (ref "D4") (pin "5") (pinfunction "EN_5") (pintype "passive"))
      (node (ref "X1") (pin "1") (pinfunction "1_1") (pintype "passive"))
    )
    (net (code "55") (name "GND") (class "Default")
      (node (ref "C1") (pin "2") (pinfunction "2_2") (pintype "passive"))
      (node (ref "C10") (pin "1") (pinfunction "1_1") (pintype "passive"))
      (node (ref "C11") (pin "1") (pinfunction "1_1") (pintype "passive"))
      (node (ref "C12") (pin "1") (pinfunction "1_1") (pintype "passive"))
      (node (ref "C2") (pin "1") (pinfunction "1_1") (pintype "passive"))
      (node (ref "C3") (pin "1") (pinfunction "1_1") (pintype "passive"))
      (node (ref "C4") (pin "1") (pinfunction "1_1") (pintype "passive"))
      (node (ref "C5") (pin "1") (pinfunction "1_1") (pintype "passive"))
      (node (ref "C6") (pin "1") (pinfunction "1_1") (pintype "passive"))
      (node (ref "C8") (pin "1") (pinfunction "1_1") (pintype "passive"))
      (node (ref "C9") (pin "1") (pinfunction "1_1") (pintype "passive"))
      (node (ref "D1") (pin "1") (pinfunction "GND_1") (pintype "power_in"))
      (node (ref "D1") (pin "21") (pinfunction "~{OE}_21") (pintype "passive"))
      (node (ref "D2") (pin "5") (pinfunction "GND_5") (pintype "power_in"))
      (node (ref "D4") (pin "1") (pinfunction "GND_1") (pintype "power_in"))
      (node (ref "D5") (pin "1") (pinfunction "BOOT0_1") (pintype "passive"))
      (node (ref "D5") (pin "15") (pinfunction "VSS_15") (pintype "power_in"))
      (node (ref "D6") (pin "1") (pinfunction "GND_1") (pintype "power_in"))
      (node (ref "D6") (pin "21") (pinfunction "~{OE}_21") (pintype "passive"))
      (node (ref "D7") (pin "1") (pinfunction "GND_1") (pintype "power_in"))
      (node (ref "D7") (pin "21") (pinfunction "~{OE}_21") (pintype "passive"))
      (node (ref "R1") (pin "1") (pinfunction "1_1") (pintype "passive"))
      (node (ref "R1") (pin "2") (pinfunction "2_2") (pintype "passive"))
      (node (ref "R14") (pin "1") (pinfunction "1_1") (pintype "passive"))
      (node (ref "R15") (pin "2") (pinfunction "2_2") (pintype "passive"))
      (node (ref "R16") (pin "2") (pinfunction "2_2") (pintype "passive"))
      (node (ref "R2") (pin "1") (pinfunction "1_1") (pintype "passive"))
      (node (ref "R2") (pin "2") (pinfunction "2_2") (pintype "passive"))
      (node (ref "R3") (pin "1") (pinfunction "1_1") (pintype "passive"))
      (node (ref "R3") (pin "2") (pinfunction "2_2") (pintype "passive"))
      (node (ref "R4") (pin "2") (pinfunction "2_2") (pintype "passive"))
      (node (ref "R5") (pin "2") (pinfunction "2_2") (pintype "passive"))
      (node (ref "X1") (pin "5") (pinfunction "5_5") (pintype "passive"))
    )
    (net (code "56") (name "Net-(D1-R-EXT)") (class "Default")
      (node (ref "D1") (pin "23") (pinfunction "R-EXT_23") (pintype "passive"))
      (node (ref "R5") (pin "1") (pinfunction "1_1") (pintype "passive"))
    )
    (net (code "57") (name "Net-(D2-DQ)") (class "Default")
      (node (ref "D2") (pin "4") (pinfunction "DQ_4") (pintype "passive"))
      (node (ref "R7") (pin "2") (pinfunction "2_2") (pintype "passive"))
      (node (ref "R8") (pin "1") (pinfunction "1_1") (pintype "passive"))
    )
    (net (code "58") (name "Net-(D3-ADJ)") (class "Default")
      (node (ref "D3") (pin "1") (pinfunction "ADJ_1") (pintype "passive"))
      (node (ref "R4") (pin "1") (pinfunction "1_1") (pintype "passive"))
      (node (ref "R6") (pin "1") (pinfunction "1_1") (pintype "passive"))
    )
    (net (code "59") (name "Net-(D4-SW)") (class "Default")
      (node (ref "C7") (pin "1") (pinfunction "1_1") (pintype "passive"))
      (node (ref "D4") (pin "2") (pinfunction "SW_2") (pintype "passive"))
      (node (ref "L1") (pin "1") (pinfunction "1_1") (pintype "passive"))
    )
    (net (code "60") (name "Net-(D4-VBST)") (class "Default")
      (node (ref "C7") (pin "2") (pinfunction "2_2") (pintype "passive"))
      (node (ref "D4") (pin "6") (pinfunction "VBST_6") (pintype "passive"))
    )
    (net (code "61") (name "Net-(D4-VFB)") (class "Default")
      (node (ref "D4") (pin "4") (pinfunction "VFB_4") (pintype "passive"))
      (node (ref "R13") (pin "1") (pinfunction "1_1") (pintype "passive"))
      (node (ref "R14") (pin "2") (pinfunction "2_2") (pintype "passive"))
    )
    (net (code "62") (name "Net-(D5-NRST)") (class "Default")
      (node (ref "D5") (pin "4") (pinfunction "NRST_4") (pintype "passive"))
      (node (ref "R12") (pin "1") (pinfunction "1_1") (pintype "passive"))
    )
    (net (code "63") (name "Net-(D5-PA10)") (class "Default")
      (node (ref "D5") (pin "17") (pinfunction "PA9_17") (pintype "passive"))
      (node (ref "D5") (pin "18") (pinfunction "PA10_18") (pintype "passive"))
      (node (ref "R9") (pin "2") (pinfunction "2_2") (pintype "passive"))
    )
    (net (code "64") (name "Net-(D5-PA13)") (class "Default")
      (node (ref "1") (pin "1") (pintype "passive"))
      (node (ref "D5") (pin "19") (pinfunction "PA13_19") (pintype "passive"))
    )
    (net (code "65") (name "Net-(D5-PA14)") (class "Default")
      (node (ref "2") (pin "1") (pintype "passive"))
      (node (ref "D5") (pin "20") (pinfunction "PA14_20") (pintype "passive"))
    )
    (net (code "66") (name "Net-(D5-PB1)") (class "Default")
      (node (ref "D5") (pin "14") (pinfunction "PB1_14") (pintype "passive"))
      (node (ref "R11") (pin "2") (pinfunction "2_2") (pintype "passive"))
    )
    (net (code "67") (name "Net-(D6-R-EXT)") (class "Default")
      (node (ref "D6") (pin "23") (pinfunction "R-EXT_23") (pintype "passive"))
      (node (ref "R15") (pin "1") (pinfunction "1_1") (pintype "passive"))
    )
    (net (code "68") (name "Net-(D7-R-EXT)") (class "Default")
      (node (ref "D7") (pin "23") (pinfunction "R-EXT_23") (pintype "passive"))
      (node (ref "R16") (pin "1") (pinfunction "1_1") (pintype "passive"))
    )
    (net (code "69") (name "Net-(R8-Pad2)") (class "Default")
      (node (ref "R8") (pin "2") (pinfunction "2_2") (pintype "passive"))
      (node (ref "R9") (pin "1") (pinfunction "1_1") (pintype "passive"))
    )
    (net (code "70") (name "unconnected-(D5-PA0-Pad6)") (class "Default")
      (node (ref "D5") (pin "6") (pinfunction "PA0_6") (pintype "passive"))
    )
    (net (code "71") (name "unconnected-(D5-PA1-Pad7)") (class "Default")
      (node (ref "D5") (pin "7") (pinfunction "PA1_7") (pintype "passive"))
    )
    (net (code "72") (name "unconnected-(D5-PA2-Pad8)") (class "Default")
      (node (ref "D5") (pin "8") (pinfunction "PA2_8") (pintype "passive"))
    )
    (net (code "73") (name "unconnected-(D5-PA3-Pad9)") (class "Default")
      (node (ref "D5") (pin "9") (pinfunction "PA3_9") (pintype "passive"))
    )
    (net (code "74") (name "unconnected-(D5-PA6-Pad12)") (class "Default")
      (node (ref "D5") (pin "12") (pinfunction "PA6_12") (pintype "passive"))
    )
    (net (code "75") (name "unconnected-(D5-PF0-OSC_IN-Pad2)") (class "Default")
      (node (ref "D5") (pin "2") (pinfunction "PF0-OSC_IN_2") (pintype "passive"))
    )
    (net (code "76") (name "unconnected-(D5-PF1-OSC_OUT-Pad3)") (class "Default")
      (node (ref "D5") (pin "3") (pinfunction "PF1-OSC_OUT_3") (pintype "passive"))
    )
    (net (code "77") (name "unconnected-(D7-SDO-Pad22)") (class "Default")
      (node (ref "D7") (pin "22") (pinfunction "SDO_22") (pintype "passive"))
    )
    (net (code "78") (name "unconnected-(D7-~{OUT0}-Pad5)") (class "Default")
      (node (ref "D7") (pin "5") (pinfunction "~{OUT0}_5") (pintype "passive"))
    )
    (net (code "79") (name "unconnected-(D7-~{OUT15}-Pad20)") (class "Default")
      (node (ref "D7") (pin "20") (pinfunction "~{OUT15}_20") (pintype "passive"))
    )
    (net (code "80") (name "unconnected-(X1-Pad2)") (class "Default")
      (node (ref "X1") (pin "2") (pinfunction "2_2") (pintype "passive"))
    )
    (net (code "81") (name "unconnected-(X1-Pad3)") (class "Default")
      (node (ref "X1") (pin "3") (pinfunction "3_3") (pintype "passive"))
    )
    (net (code "82") (name "unconnected-(X1-Pad4)") (class "Default")
      (node (ref "X1") (pin "4") (pinfunction "4_4") (pintype "passive"))
    )
  )
)
